# IR_Signal_Conditioning-v1_0.net
KiCad netlist of a schematic drawn in EAGLE
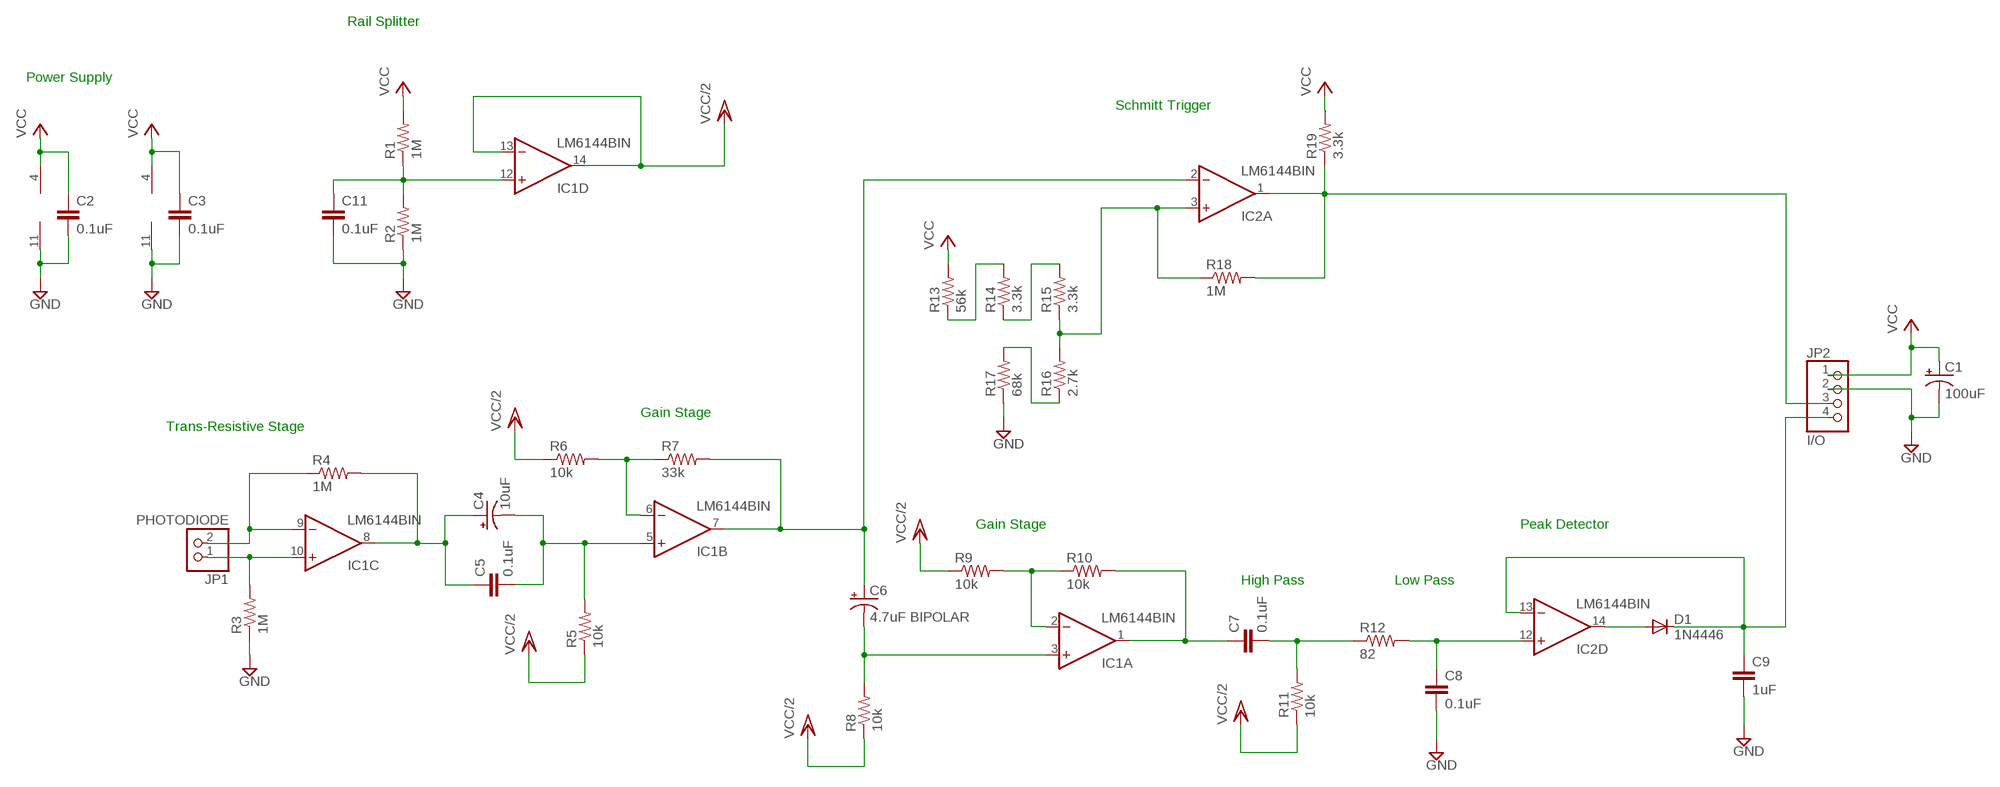
[diagram p0: schematic, sheet 1]

(export (version "E")
  (design (tool "Eeschema 10.0.6"))
  (components
    (comp (ref "C1")
      (value "100uF")
      (footprint "eagle-import:E2-5")
      (libsource (lib "eagle-import") (part "CPOL-USE2-5"))
    )
    (comp (ref "C2")
      (value "0.1uF")
      (footprint "eagle-import:C0805")
      (libsource (lib "eagle-import") (part "C-EUC0805"))
    )
    (comp (ref "C3")
      (value "0.1uF")
      (footprint "eagle-import:C0805")
      (libsource (lib "eagle-import") (part "C-EUC0805"))
    )
    (comp (ref "C4")
      (value "10uF")
      (footprint "eagle-import:E2-5")
      (libsource (lib "eagle-import") (part "CPOL-USE2-5"))
    )
    (comp (ref "C5")
      (value "0.1uF")
      (footprint "eagle-import:C0805")
      (libsource (lib "eagle-import") (part "C-EUC0805"))
    )
    (comp (ref "C6")
      (value "4.7uF BIPOLAR")
      (footprint "eagle-import:E2-5")
      (libsource (lib "eagle-import") (part "CPOL-USE2-5"))
    )
    (comp (ref "C7")
      (value "0.1uF")
      (footprint "eagle-import:C0805")
      (libsource (lib "eagle-import") (part "C-EUC0805"))
    )
    (comp (ref "C8")
      (value "0.1uF")
      (footprint "eagle-import:C0805")
      (libsource (lib "eagle-import") (part "C-EUC0805"))
    )
    (comp (ref "C9")
      (value "1uF")
      (footprint "eagle-import:C0805")
      (libsource (lib "eagle-import") (part "C-EUC0805"))
    )
    (comp (ref "C11")
      (value "0.1uF")
      (footprint "eagle-import:C0805")
      (libsource (lib "eagle-import") (part "C-EUC0805"))
    )
    (comp (ref "D1")
      (value "1N4446")
      (footprint "eagle-import:DO35-10")
      (libsource (lib "eagle-import") (part "1N4446"))
    )
    (comp (ref "IC1")
      (value "LM6144BIN")
      (footprint "eagle-import:DIL14")
      (libsource (lib "eagle-import") (part "LM2902N"))
    )
    (comp (ref "IC2")
      (value "LM6144BIN")
      (footprint "eagle-import:DIL14")
      (libsource (lib "eagle-import") (part "LM2902N"))
    )
    (comp (ref "JP1")
      (value "PHOTODIODE")
      (footprint "eagle-import:1X02")
      (libsource (lib "eagle-import") (part "PINHD-1X2"))
    )
    (comp (ref "JP2")
      (value "I/O")
      (footprint "eagle-import:1X04")
      (libsource (lib "eagle-import") (part "PINHD-1X4"))
    )
    (comp (ref "R1")
      (value "1M")
      (footprint "eagle-import:R0805")
      (libsource (lib "eagle-import") (part "R-US_R0805"))
    )
    (comp (ref "R2")
      (value "1M")
      (footprint "eagle-import:R0805")
      (libsource (lib "eagle-import") (part "R-US_R0805"))
    )
    (comp (ref "R3")
      (value "1M")
      (footprint "eagle-import:R0805")
      (libsource (lib "eagle-import") (part "R-US_R0805"))
    )
    (comp (ref "R4")
      (value "1M")
      (footprint "eagle-import:R0805")
      (libsource (lib "eagle-import") (part "R-US_R0805"))
    )
    (comp (ref "R5")
      (value "10k")
      (footprint "eagle-import:R0805")
      (libsource (lib "eagle-import") (part "R-US_R0805"))
    )
    (comp (ref "R6")
      (value "10k")
      (footprint "eagle-import:R0805")
      (libsource (lib "eagle-import") (part "R-US_R0805"))
    )
    (comp (ref "R7")
      (value "33k")
      (footprint "eagle-import:R0805")
      (libsource (lib "eagle-import") (part "R-US_R0805"))
    )
    (comp (ref "R8")
      (value "10k")
      (footprint "eagle-import:R0805")
      (libsource (lib "eagle-import") (part "R-US_R0805"))
    )
    (comp (ref "R9")
      (value "10k")
      (footprint "eagle-import:R0805")
      (libsource (lib "eagle-import") (part "R-US_R0805"))
    )
    (comp (ref "R10")
      (value "10k")
      (footprint "eagle-import:R0805")
      (libsource (lib "eagle-import") (part "R-US_R0805"))
    )
    (comp (ref "R11")
      (value "10k")
      (footprint "eagle-import:R0805")
      (libsource (lib "eagle-import") (part "R-US_R0805"))
    )
    (comp (ref "R12")
      (value "82")
      (footprint "eagle-import:R0805")
      (libsource (lib "eagle-import") (part "R-US_R0805"))
    )
    (comp (ref "R13")
      (value "56k")
      (footprint "eagle-import:R0805")
      (libsource (lib "eagle-import") (part "R-US_R0805"))
    )
    (comp (ref "R14")
      (value "3.3k")
      (footprint "eagle-import:R0805")
      (libsource (lib "eagle-import") (part "R-US_R0805"))
    )
    (comp (ref "R15")
      (value "3.3k")
      (footprint "eagle-import:R0805")
      (libsource (lib "eagle-import") (part "R-US_R0805"))
    )
    (comp (ref "R16")
      (value "2.7k")
      (footprint "eagle-import:R0805")
      (libsource (lib "eagle-import") (part "R-US_R0805"))
    )
    (comp (ref "R17")
      (value "68k")
      (footprint "eagle-import:R0805")
      (libsource (lib "eagle-import") (part "R-US_R0805"))
    )
    (comp (ref "R18")
      (value "1M")
      (footprint "eagle-import:R0805")
      (libsource (lib "eagle-import") (part "R-US_R0805"))
    )
    (comp (ref "R19")
      (value "3.3k")
      (footprint "eagle-import:R0805")
      (libsource (lib "eagle-import") (part "R-US_R0805"))
    )
  )
  (nets
    (net (code "1") (name "GND") (class "Default")
      (node (ref "C1") (pin "-") (pinfunction "-_-") (pintype "passive"))
      (node (ref "C11") (pin "2") (pinfunction "2_2") (pintype "passive"))
      (node (ref "C2") (pin "2") (pinfunction "2_2") (pintype "passive"))
      (node (ref "C3") (pin "2") (pinfunction "2_2") (pintype "passive"))
      (node (ref "C8") (pin "2") (pinfunction "2_2") (pintype "passive"))
      (node (ref "C9") (pin "2") (pinfunction "2_2") (pintype "passive"))
      (node (ref "IC1") (pin "11") (pinfunction "V-_11") (pintype "power_in"))
      (node (ref "IC2") (pin "11") (pinfunction "V-_11") (pintype "power_in"))
      (node (ref "JP2") (pin "2") (pinfunction "2_2") (pintype "passive"))
      (node (ref "R17") (pin "1") (pinfunction "1_1") (pintype "passive"))
      (node (ref "R2") (pin "1") (pinfunction "1_1") (pintype "passive"))
      (node (ref "R3") (pin "1") (pinfunction "1_1") (pintype "passive"))
    )
    (net (code "2") (name "Net-(C7-Pad2)") (class "Default")
      (node (ref "C7") (pin "2") (pinfunction "2_2") (pintype "passive"))
      (node (ref "R11") (pin "2") (pinfunction "2_2") (pintype "passive"))
      (node (ref "R12") (pin "1") (pinfunction "1_1") (pintype "passive"))
    )
    (net (code "3") (name "Net-(IC1A-+IN)") (class "Default")
      (node (ref "C6") (pin "-") (pinfunction "-_-") (pintype "passive"))
      (node (ref "IC1") (pin "3") (pinfunction "+IN_3") (pintype "input"))
      (node (ref "R8") (pin "2") (pinfunction "2_2") (pintype "passive"))
    )
    (net (code "4") (name "Net-(IC1A--IN)") (class "Default")
      (node (ref "IC1") (pin "2") (pinfunction "-IN_2") (pintype "input"))
      (node (ref "R10") (pin "1") (pinfunction "1_1") (pintype "passive"))
      (node (ref "R9") (pin "2") (pinfunction "2_2") (pintype "passive"))
    )
    (net (code "5") (name "Net-(IC1A-OUT)") (class "Default")
      (node (ref "C7") (pin "1") (pinfunction "1_1") (pintype "passive"))
      (node (ref "IC1") (pin "1") (pinfunction "OUT_1") (pintype "output"))
      (node (ref "R10") (pin "2") (pinfunction "2_2") (pintype "passive"))
    )
    (net (code "6") (name "Net-(IC1B-+IN)") (class "Default")
      (node (ref "C4") (pin "-") (pinfunction "-_-") (pintype "passive"))
      (node (ref "C5") (pin "2") (pinfunction "2_2") (pintype "passive"))
      (node (ref "IC1") (pin "5") (pinfunction "+IN_5") (pintype "input"))
      (node (ref "R5") (pin "2") (pinfunction "2_2") (pintype "passive"))
    )
    (net (code "7") (name "Net-(IC1B--IN)") (class "Default")
      (node (ref "IC1") (pin "6") (pinfunction "-IN_6") (pintype "input"))
      (node (ref "R6") (pin "2") (pinfunction "2_2") (pintype "passive"))
      (node (ref "R7") (pin "1") (pinfunction "1_1") (pintype "passive"))
    )
    (net (code "8") (name "Net-(IC1B-OUT)") (class "Default")
      (node (ref "C6") (pin "+") (pinfunction "+_+") (pintype "passive"))
      (node (ref "IC1") (pin "7") (pinfunction "OUT_7") (pintype "output"))
      (node (ref "IC2") (pin "2") (pinfunction "-IN_2") (pintype "input"))
      (node (ref "R7") (pin "2") (pinfunction "2_2") (pintype "passive"))
    )
    (net (code "9") (name "Net-(IC1C-+IN)") (class "Default")
      (node (ref "IC1") (pin "10") (pinfunction "+IN_10") (pintype "input"))
      (node (ref "JP1") (pin "1") (pinfunction "1_1") (pintype "passive"))
      (node (ref "R3") (pin "2") (pinfunction "2_2") (pintype "passive"))
    )
    (net (code "10") (name "Net-(IC1C--IN)") (class "Default")
      (node (ref "IC1") (pin "9") (pinfunction "-IN_9") (pintype "input"))
      (node (ref "JP1") (pin "2") (pinfunction "2_2") (pintype "passive"))
      (node (ref "R4") (pin "1") (pinfunction "1_1") (pintype "passive"))
    )
    (net (code "11") (name "Net-(IC1C-OUT)") (class "Default")
      (node (ref "C4") (pin "+") (pinfunction "+_+") (pintype "passive"))
      (node (ref "C5") (pin "1") (pinfunction "1_1") (pintype "passive"))
      (node (ref "IC1") (pin "8") (pinfunction "OUT_8") (pintype "output"))
      (node (ref "R4") (pin "2") (pinfunction "2_2") (pintype "passive"))
    )
    (net (code "12") (name "Net-(IC1D-+IN)") (class "Default")
      (node (ref "C11") (pin "1") (pinfunction "1_1") (pintype "passive"))
      (node (ref "IC1") (pin "12") (pinfunction "+IN_12") (pintype "input"))
      (node (ref "R1") (pin "1") (pinfunction "1_1") (pintype "passive"))
      (node (ref "R2") (pin "2") (pinfunction "2_2") (pintype "passive"))
    )
    (net (code "13") (name "Net-(IC2A-+IN)") (class "Default")
      (node (ref "IC2") (pin "3") (pinfunction "+IN_3") (pintype "input"))
      (node (ref "R15") (pin "1") (pinfunction "1_1") (pintype "passive"))
      (node (ref "R16") (pin "2") (pinfunction "2_2") (pintype "passive"))
      (node (ref "R18") (pin "1") (pinfunction "1_1") (pintype "passive"))
    )
    (net (code "14") (name "Net-(IC2A-OUT)") (class "Default")
      (node (ref "IC2") (pin "1") (pinfunction "OUT_1") (pintype "output"))
      (node (ref "JP2") (pin "3") (pinfunction "3_3") (pintype "passive"))
      (node (ref "R18") (pin "2") (pinfunction "2_2") (pintype "passive"))
      (node (ref "R19") (pin "1") (pinfunction "1_1") (pintype "passive"))
    )
    (net (code "15") (name "Net-(IC2D-+IN)") (class "Default")
      (node (ref "C8") (pin "1") (pinfunction "1_1") (pintype "passive"))
      (node (ref "IC2") (pin "12") (pinfunction "+IN_12") (pintype "input"))
      (node (ref "R12") (pin "2") (pinfunction "2_2") (pintype "passive"))
    )
    (net (code "16") (name "Net-(IC2D--IN)") (class "Default")
      (node (ref "C9") (pin "1") (pinfunction "1_1") (pintype "passive"))
      (node (ref "D1") (pin "C") (pinfunction "C_C") (pintype "passive"))
      (node (ref "IC2") (pin "13") (pinfunction "-IN_13") (pintype "input"))
      (node (ref "JP2") (pin "4") (pinfunction "4_4") (pintype "passive"))
    )
    (net (code "17") (name "Net-(IC2D-OUT)") (class "Default")
      (node (ref "D1") (pin "A") (pinfunction "A_A") (pintype "passive"))
      (node (ref "IC2") (pin "14") (pinfunction "OUT_14") (pintype "output"))
    )
    (net (code "18") (name "Net-(R13-Pad1)") (class "Default")
      (node (ref "R13") (pin "1") (pinfunction "1_1") (pintype "passive"))
      (node (ref "R14") (pin "2") (pinfunction "2_2") (pintype "passive"))
    )
    (net (code "19") (name "Net-(R14-Pad1)") (class "Default")
      (node (ref "R14") (pin "1") (pinfunction "1_1") (pintype "passive"))
      (node (ref "R15") (pin "2") (pinfunction "2_2") (pintype "passive"))
    )
    (net (code "20") (name "Net-(R16-Pad1)") (class "Default")
      (node (ref "R16") (pin "1") (pinfunction "1_1") (pintype "passive"))
      (node (ref "R17") (pin "2") (pinfunction "2_2") (pintype "passive"))
    )
    (net (code "21") (name "VCC") (class "Default")
      (node (ref "C1") (pin "+") (pinfunction "+_+") (pintype "passive"))
      (node (ref "C2") (pin "1") (pinfunction "1_1") (pintype "passive"))
      (node (ref "C3") (pin "1") (pinfunction "1_1") (pintype "passive"))
      (node (ref "IC1") (pin "4") (pinfunction "V+_4") (pintype "power_in"))
      (node (ref "IC2") (pin "4") (pinfunction "V+_4") (pintype "power_in"))
      (node (ref "JP2") (pin "1") (pinfunction "1_1") (pintype "passive"))
      (node (ref "R1") (pin "2") (pinfunction "2_2") (pintype "passive"))
      (node (ref "R13") (pin "2") (pinfunction "2_2") (pintype "passive"))
      (node (ref "R19") (pin "2") (pinfunction "2_2") (pintype "passive"))
    )
    (net (code "22") (name "VCC{slash}2") (class "Default")
      (node (ref "IC1") (pin "13") (pinfunction "-IN_13") (pintype "input"))
      (node (ref "IC1") (pin "14") (pinfunction "OUT_14") (pintype "output"))
      (node (ref "R11") (pin "1") (pinfunction "1_1") (pintype "passive"))
      (node (ref "R5") (pin "1") (pinfunction "1_1") (pintype "passive"))
      (node (ref "R6") (pin "1") (pinfunction "1_1") (pintype "passive"))
      (node (ref "R8") (pin "1") (pinfunction "1_1") (pintype "passive"))
      (node (ref "R9") (pin "1") (pinfunction "1_1") (pintype "passive"))
    )
  )
)
